# 5V_EFuse.net
KiCad netlist of a schematic drawn in Altium Designer
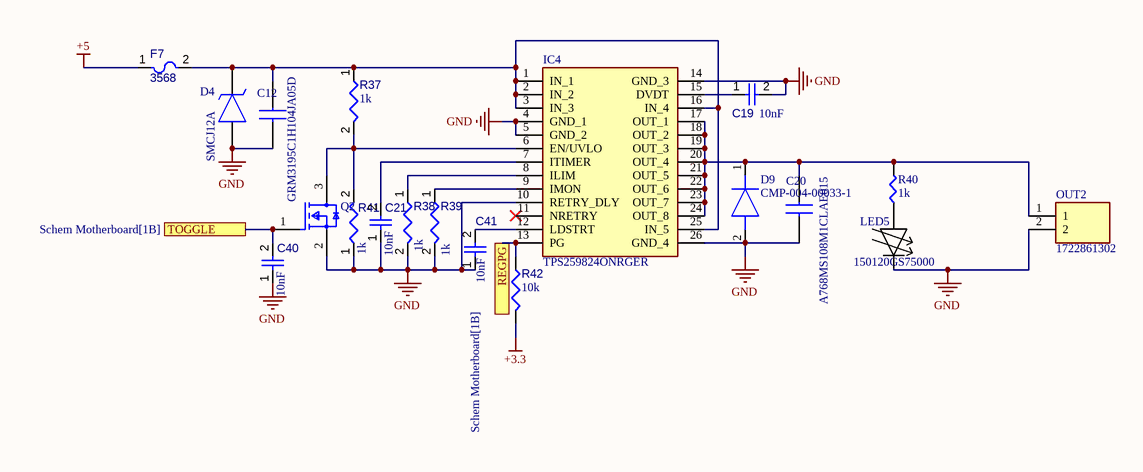
[diagram p0: 5V EFuse.SchDoc]

(export (version "E")
  (design (tool "Eeschema 10.0.6"))
  (components
    (comp (ref "C12")
      (value "GRM3195C1H104JA05D")
      (footprint "SamacSys:CAPC3216X95N")
      (description "Capacitor")
      (fields (field (name "MOUSER PART NUMBER") "81-GRM3195C1H104JA5D"))
      (libsource (lib "*") (part "GRM3195C1H104JA05D"))
    )
    (comp (ref "C19")
      (value "10nF")
      (footprint "CAPC0402(1005)60_L")
      (description "Chip Capacitor, 10nF +/-20%, 50V, 0402, Thickness 0.6 mm")
      (fields (field (name "TOLERANCE") "5%") (field (name "Comment") "Capacitor 10nF +/-20% 50V 0402"))
      (libsource (lib "CPRT Workspace") (part "CAP-NP-2"))
    )
    (comp (ref "C20")
      (value "A768MS108M1CLAE015")
      (footprint "SamacSys:CAPAE1030X1030N")
      (description "Capacitor")
      (fields (field (name "MOUSER PART NUMBER") "80-A768MS108M1CLAE15"))
      (libsource (lib "*") (part "A768MS108M1CLAE015"))
    )
    (comp (ref "C21")
      (value "10nF")
      (footprint "CAPC0402(1005)60_L")
      (description "Chip Capacitor, 10nF +/-20%, 50V, 0402, Thickness 0.6 mm")
      (fields (field (name "TOLERANCE") "5%") (field (name "Comment") "Capacitor 10nF +/-20% 50V 0402"))
      (libsource (lib "CPRT Workspace") (part "CAP-NP-2"))
    )
    (comp (ref "C40")
      (value "10nF")
      (footprint "CAPC0402(1005)60_L")
      (description "Chip Capacitor, 10nF +/-20%, 50V, 0402, Thickness 0.6 mm")
      (fields (field (name "TOLERANCE") "5%") (field (name "Comment") "Capacitor 10nF +/-20% 50V 0402"))
      (libsource (lib "CPRT Workspace") (part "CAP-NP-2"))
    )
    (comp (ref "C41")
      (value "10nF")
      (footprint "CAPC0402(1005)60_L")
      (description "Chip Capacitor, 10nF +/-20%, 50V, 0402, Thickness 0.6 mm")
      (fields (field (name "TOLERANCE") "5%") (field (name "Comment") "Capacitor 10nF +/-20% 50V 0402"))
      (libsource (lib "CPRT Workspace") (part "CAP-NP-2"))
    )
    (comp (ref "D4")
      (value "SMCJ12A")
      (footprint "SamacSys:SMCJ12A")
      (description "TVS Diode (Uni-directional)")
      (fields (field (name "MOUSER PART NUMBER") "821-SMCJ12A"))
      (libsource (lib "*") (part "SMCJ12A"))
    )
    (comp (ref "D9")
      (value "CMP-004-00033-1")
      (footprint "DIOM7959X250N")
      (description "Schottky Diodes & Rectifiers 20V 5A")
      (fields
        (field (name "MANUFACTURER_PART_NUMBER") "B520C-13-F")
        (field (name "MOUSER PART NUMBER") "621-B520C-F")
      )
      (libsource (lib "CPRT Workspace") (part "CMP-004-00033-1"))
    )
    (comp (ref "F7")
      (value "3568")
      (footprint "KSTN-3568_V")
      (description "Fuses/Accessories")
      (libsource (lib "CPRT Workspace") (part "FUSE-2"))
    )
    (comp (ref "IC4")
      (value "TPS259824ONRGER")
      (footprint "SamacSys:TPS259824LNRGER")
      (description "Integrated Circuit")
      (fields (field (name "MOUSER PART NUMBER") "595-TPS259824ONRGER"))
      (libsource (lib "CPRT Workspace") (part "CMP-031-00019-1"))
    )
    (comp (ref "LED5")
      (value "150120GS75000")
      (footprint "150120GS75000")
      (description "Green Status LED 1206")
      (libsource (lib "CPRT Workspace") (part "150120GS75000"))
    )
    (comp (ref "OUT2")
      (value "1722861302")
      (footprint "SamacSys:1722861302")
      (description "Connector")
      (libsource (lib "*") (part "1722861302"))
    )
    (comp (ref "Q2")
      (value "IRFML8244TRPBF")
      (footprint "FP-PG-SOT23-3-IPC_B")
      (libsource (lib "CPRT Workspace") (part "381a366367e4312d0f7d2747150cb42"))
    )
    (comp (ref "R37")
      (value "1k")
      (footprint "RESC0402(1005)_L")
      (description "1K 0.063W 5% 0402 (1005 Metric)  SMD")
      (fields (field (name "POWER") "63mW") (field (name "TOLERANCE") "5%"))
      (libsource (lib "CPRT Workspace") (part "1KR2J"))
    )
    (comp (ref "R38")
      (value "1k")
      (footprint "RESC0402(1005)_L")
      (description "1K 0.063W 5% 0402 (1005 Metric)  SMD")
      (fields (field (name "POWER") "63mW") (field (name "TOLERANCE") "5%"))
      (libsource (lib "CPRT Workspace") (part "1KR2J"))
    )
    (comp (ref "R39")
      (value "1k")
      (footprint "RESC0402(1005)_L")
      (description "1K 0.063W 5% 0402 (1005 Metric)  SMD")
      (fields (field (name "POWER") "63mW") (field (name "TOLERANCE") "5%"))
      (libsource (lib "CPRT Workspace") (part "1KR2J"))
    )
    (comp (ref "R40")
      (value "1k")
      (footprint "SMD-1206-RES")
      (description "RES SMD 1K OHM 5% 2/3W 1206")
      (fields
        (field (name "DIGI-KEY PART NUMBER") "P1.0KALCT-ND")
        (field (name "PART NUMBER") "ERJ-P08J102V")
      )
      (libsource (lib "CPRT Workspace") (part "Symbol"))
    )
    (comp (ref "R41")
      (value "1k")
      (footprint "RESC0402(1005)_L")
      (description "1K 0.063W 5% 0402 (1005 Metric)  SMD")
      (fields (field (name "POWER") "63mW") (field (name "TOLERANCE") "5%"))
      (libsource (lib "CPRT Workspace") (part "1KR2J"))
    )
    (comp (ref "R42")
      (value "10k")
      (footprint "RESC0402(1005)_L")
      (description "10 kOhms ±0.1% 0.063W, 1/16W Chip Resistor 0402 (1005 Metric) Automotive AEC-Q200 Thin Film")
      (fields (field (name "POWER") "63mW") (field (name "TOLERANCE") "5%"))
      (libsource (lib "") (part "1KR2J_1"))
    )
  )
  (nets
    (net (code "1") (name "+3.3") (class "Default")
      (node (ref "R42") (pin "2") (pinfunction "2_2") (pintype "passive"))
    )
    (net (code "2") (name "+5") (class "Default")
      (node (ref "F7") (pin "1") (pinfunction "1_1") (pintype "passive"))
    )
    (net (code "3") (name "/REGPG") (class "Default")
      (node (ref "IC4") (pin "13") (pinfunction "PG_13") (pintype "passive"))
      (node (ref "R42") (pin "1") (pinfunction "1_1") (pintype "passive"))
    )
    (net (code "4") (name "/TOGGLE") (class "Default")
      (node (ref "C40") (pin "2") (pinfunction "2_2") (pintype "passive"))
      (node (ref "Q2") (pin "1") (pinfunction "G_1") (pintype "passive"))
    )
    (net (code "5") (name "GND") (class "Default")
      (node (ref "C12") (pin "2") (pinfunction "2_2") (pintype "passive"))
      (node (ref "C19") (pin "2") (pinfunction "2_2") (pintype "passive"))
      (node (ref "C20") (pin "2") (pinfunction "-_2") (pintype "passive"))
      (node (ref "C21") (pin "1") (pinfunction "1_1") (pintype "passive"))
      (node (ref "C40") (pin "1") (pinfunction "1_1") (pintype "passive"))
      (node (ref "C41") (pin "1") (pinfunction "1_1") (pintype "passive"))
      (node (ref "D4") (pin "2") (pinfunction "A_2") (pintype "passive"))
      (node (ref "D9") (pin "2") (pinfunction "A_2") (pintype "passive"))
      (node (ref "IC4") (pin "10") (pinfunction "RETRY_DLY_10") (pintype "passive"))
      (node (ref "IC4") (pin "14") (pinfunction "GND_3_14") (pintype "passive"))
      (node (ref "IC4") (pin "26") (pinfunction "GND_4_26") (pintype "passive"))
      (node (ref "IC4") (pin "4") (pinfunction "GND_1_4") (pintype "passive"))
      (node (ref "IC4") (pin "5") (pinfunction "GND_2_5") (pintype "passive"))
      (node (ref "LED5") (pin "1") (pinfunction "1_1") (pintype "passive"))
      (node (ref "OUT2") (pin "2") (pinfunction "2_2") (pintype "passive"))
      (node (ref "Q2") (pin "2") (pinfunction "S_2") (pintype "passive"))
      (node (ref "R38") (pin "2") (pinfunction "2_2") (pintype "passive"))
      (node (ref "R39") (pin "2") (pinfunction "2_2") (pintype "passive"))
      (node (ref "R41") (pin "1") (pinfunction "1_1") (pintype "passive"))
    )
    (net (code "6") (name "Net-(C20-+)") (class "Default")
      (node (ref "C20") (pin "1") (pinfunction "+_1") (pintype "passive"))
      (node (ref "D9") (pin "1") (pinfunction "K_1") (pintype "passive"))
      (node (ref "IC4") (pin "17") (pinfunction "OUT_1_17") (pintype "passive"))
      (node (ref "IC4") (pin "18") (pinfunction "OUT_2_18") (pintype "passive"))
      (node (ref "IC4") (pin "19") (pinfunction "OUT_3_19") (pintype "passive"))
      (node (ref "IC4") (pin "20") (pinfunction "OUT_4_20") (pintype "passive"))
      (node (ref "IC4") (pin "21") (pinfunction "OUT_5_21") (pintype "passive"))
      (node (ref "IC4") (pin "22") (pinfunction "OUT_6_22") (pintype "passive"))
      (node (ref "IC4") (pin "23") (pinfunction "OUT_7_23") (pintype "passive"))
      (node (ref "IC4") (pin "24") (pinfunction "OUT_8_24") (pintype "passive"))
      (node (ref "OUT2") (pin "1") (pinfunction "1_1") (pintype "passive"))
      (node (ref "R40") (pin "2") (pinfunction "2_2") (pintype "passive"))
    )
    (net (code "7") (name "Net-(D4-K)") (class "Default")
      (node (ref "C12") (pin "1") (pinfunction "1_1") (pintype "passive"))
      (node (ref "D4") (pin "1") (pinfunction "K_1") (pintype "passive"))
      (node (ref "F7") (pin "2") (pinfunction "2_2") (pintype "passive"))
      (node (ref "IC4") (pin "1") (pinfunction "IN_1_1") (pintype "passive"))
      (node (ref "IC4") (pin "16") (pinfunction "IN_4_16") (pintype "passive"))
      (node (ref "IC4") (pin "2") (pinfunction "IN_2_2") (pintype "passive"))
      (node (ref "IC4") (pin "25") (pinfunction "IN_5_25") (pintype "passive"))
      (node (ref "IC4") (pin "3") (pinfunction "IN_3_3") (pintype "passive"))
      (node (ref "R37") (pin "1") (pinfunction "1_1") (pintype "passive"))
    )
    (net (code "8") (name "Net-(IC4-DVDT)") (class "Default")
      (node (ref "C19") (pin "1") (pinfunction "1_1") (pintype "passive"))
      (node (ref "IC4") (pin "15") (pinfunction "DVDT_15") (pintype "passive"))
    )
    (net (code "9") (name "Net-(IC4-EN{slash}UVLO)") (class "Default")
      (node (ref "IC4") (pin "6") (pinfunction "EN/UVLO_6") (pintype "passive"))
      (node (ref "Q2") (pin "3") (pinfunction "D_3") (pintype "passive"))
      (node (ref "R37") (pin "2") (pinfunction "2_2") (pintype "passive"))
      (node (ref "R41") (pin "2") (pinfunction "2_2") (pintype "passive"))
    )
    (net (code "10") (name "Net-(IC4-ILIM)") (class "Default")
      (node (ref "IC4") (pin "8") (pinfunction "ILIM_8") (pintype "passive"))
      (node (ref "R38") (pin "1") (pinfunction "1_1") (pintype "passive"))
    )
    (net (code "11") (name "Net-(IC4-IMON)") (class "Default")
      (node (ref "IC4") (pin "9") (pinfunction "IMON_9") (pintype "passive"))
      (node (ref "R39") (pin "1") (pinfunction "1_1") (pintype "passive"))
    )
    (net (code "12") (name "Net-(IC4-ITIMER)") (class "Default")
      (node (ref "C21") (pin "2") (pinfunction "2_2") (pintype "passive"))
      (node (ref "IC4") (pin "7") (pinfunction "ITIMER_7") (pintype "passive"))
    )
    (net (code "13") (name "Net-(IC4-LDSTRT)") (class "Default")
      (node (ref "C41") (pin "2") (pinfunction "2_2") (pintype "passive"))
      (node (ref "IC4") (pin "12") (pinfunction "LDSTRT_12") (pintype "passive"))
    )
    (net (code "14") (name "Net-(LED5-Pad2)") (class "Default")
      (node (ref "LED5") (pin "2") (pinfunction "2_2") (pintype "passive"))
      (node (ref "R40") (pin "1") (pinfunction "1_1") (pintype "passive"))
    )
    (net (code "15") (name "unconnected-(IC4-NRETRY-Pad11)") (class "Default")
      (node (ref "IC4") (pin "11") (pinfunction "NRETRY_11") (pintype "passive+no_connect"))
    )
  )
)
